# LevelShifter.net
KiCad netlist of a schematic drawn in Altium Designer
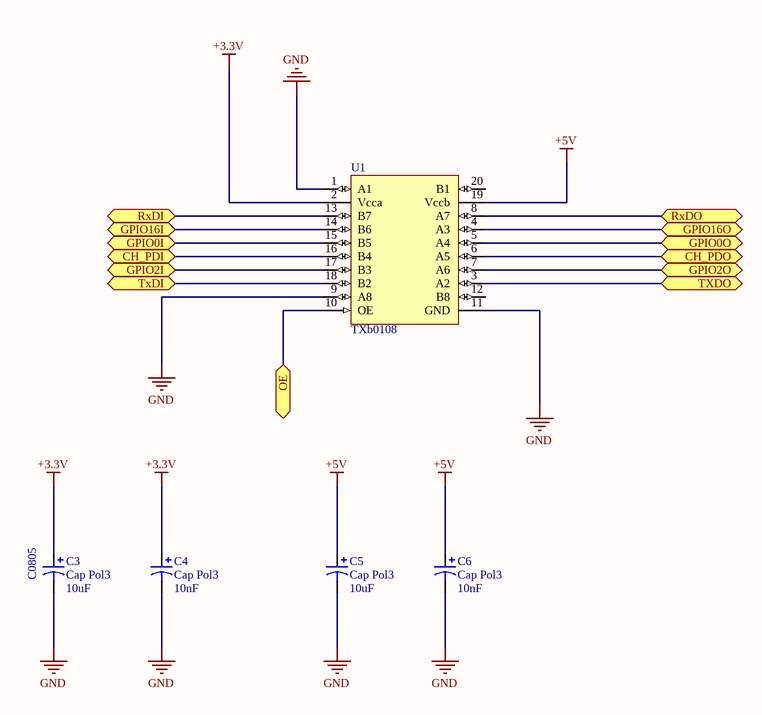
[diagram p0: LevelShifter.SchDoc]

(export (version "E")
  (design (tool "Eeschema 10.0.6"))
  (components
    (comp (ref "C3")
      (value "Cap Pol3")
      (footprint "C0805")
      (description "Polarized Capacitor (Surface Mount)")
      (fields
        (field (name "PACKAGEREFERENCE") "C0805")
        (field (name "ALTIUM_VALUE") "10uF")
        (field (name "PUBLISHER") "Altium Limited")
      )
      (libsource (lib "Miscellaneous Devices") (part "Cap Pol3"))
    )
    (comp (ref "C4")
      (value "Cap Pol3")
      (footprint "C0805")
      (description "Polarized Capacitor (Surface Mount)")
      (fields (field (name "ALTIUM_VALUE") "10nF") (field (name "PUBLISHER") "Altium Limited"))
      (libsource (lib "Miscellaneous Devices") (part "Cap Pol3"))
    )
    (comp (ref "C5")
      (value "Cap Pol3")
      (footprint "C0805")
      (description "Polarized Capacitor (Surface Mount)")
      (fields (field (name "ALTIUM_VALUE") "10uF") (field (name "PUBLISHER") "Altium Limited"))
      (libsource (lib "Miscellaneous Devices") (part "Cap Pol3"))
    )
    (comp (ref "C6")
      (value "Cap Pol3")
      (footprint "C0805")
      (description "Polarized Capacitor (Surface Mount)")
      (fields (field (name "ALTIUM_VALUE") "10nF") (field (name "PUBLISHER") "Altium Limited"))
      (libsource (lib "Miscellaneous Devices") (part "Cap Pol3"))
    )
    (comp (ref "U1") (value "TXb0108") (footprint "TXB0108") (libsource (lib "TXB0108") (part "TXb0108")))
  )
  (nets
    (net (code "1") (name "+3.3V") (class "Default")
      (node (ref "C3") (pin "1") (pinfunction "1_1") (pintype "passive"))
      (node (ref "C4") (pin "1") (pinfunction "1_1") (pintype "passive"))
      (node (ref "U1") (pin "2") (pinfunction "Vcca_2") (pintype "power_in"))
    )
    (net (code "2") (name "+5V") (class "Default")
      (node (ref "C5") (pin "1") (pinfunction "1_1") (pintype "passive"))
      (node (ref "C6") (pin "1") (pinfunction "1_1") (pintype "passive"))
      (node (ref "U1") (pin "19") (pinfunction "Vccb_19") (pintype "power_in"))
    )
    (net (code "3") (name "/CH_PDI") (class "Default")
      (node (ref "U1") (pin "16") (pinfunction "B4_16") (pintype "bidirectional"))
    )
    (net (code "4") (name "/CH_PDO") (class "Default")
      (node (ref "U1") (pin "6") (pinfunction "A5_6") (pintype "bidirectional"))
    )
    (net (code "5") (name "/GPIO0I") (class "Default")
      (node (ref "U1") (pin "15") (pinfunction "B5_15") (pintype "bidirectional"))
    )
    (net (code "6") (name "/GPIO0O") (class "Default")
      (node (ref "U1") (pin "5") (pinfunction "A4_5") (pintype "bidirectional"))
    )
    (net (code "7") (name "/GPIO2I") (class "Default")
      (node (ref "U1") (pin "17") (pinfunction "B3_17") (pintype "bidirectional"))
    )
    (net (code "8") (name "/GPIO2O") (class "Default")
      (node (ref "U1") (pin "7") (pinfunction "A6_7") (pintype "bidirectional"))
    )
    (net (code "9") (name "/GPIO16I") (class "Default")
      (node (ref "U1") (pin "14") (pinfunction "B6_14") (pintype "bidirectional"))
    )
    (net (code "10") (name "/GPIO16O") (class "Default")
      (node (ref "U1") (pin "4") (pinfunction "A3_4") (pintype "bidirectional"))
    )
    (net (code "11") (name "/OE") (class "Default")
      (node (ref "U1") (pin "10") (pinfunction "OE_10") (pintype "input"))
    )
    (net (code "12") (name "/RxDI") (class "Default")
      (node (ref "U1") (pin "13") (pinfunction "B7_13") (pintype "bidirectional"))
    )
    (net (code "13") (name "/RxDO") (class "Default")
      (node (ref "U1") (pin "8") (pinfunction "A7_8") (pintype "bidirectional"))
    )
    (net (code "14") (name "/TXDO") (class "Default")
      (node (ref "U1") (pin "3") (pinfunction "A2_3") (pintype "bidirectional"))
    )
    (net (code "15") (name "/TxDI") (class "Default")
      (node (ref "U1") (pin "18") (pinfunction "B2_18") (pintype "bidirectional"))
    )
    (net (code "16") (name "GND") (class "Default")
      (node (ref "C3") (pin "2") (pinfunction "2_2") (pintype "passive"))
      (node (ref "C4") (pin "2") (pinfunction "2_2") (pintype "passive"))
      (node (ref "C5") (pin "2") (pinfunction "2_2") (pintype "passive"))
      (node (ref "C6") (pin "2") (pinfunction "2_2") (pintype "passive"))
      (node (ref "U1") (pin "1") (pinfunction "A1_1") (pintype "bidirectional"))
      (node (ref "U1") (pin "11") (pinfunction "GND_11") (pintype "power_in"))
      (node (ref "U1") (pin "9") (pinfunction "A8_9") (pintype "bidirectional"))
    )
    (net (code "17") (name "unconnected-(U1-B1-Pad20)") (class "Default")
      (node (ref "U1") (pin "20") (pinfunction "B1_20") (pintype "bidirectional"))
    )
    (net (code "18") (name "unconnected-(U1-B8-Pad12)") (class "Default")
      (node (ref "U1") (pin "12") (pinfunction "B8_12") (pintype "bidirectional"))
    )
  )
)
